# untitled.net
KiCad netlist of a schematic drawn in EAGLE
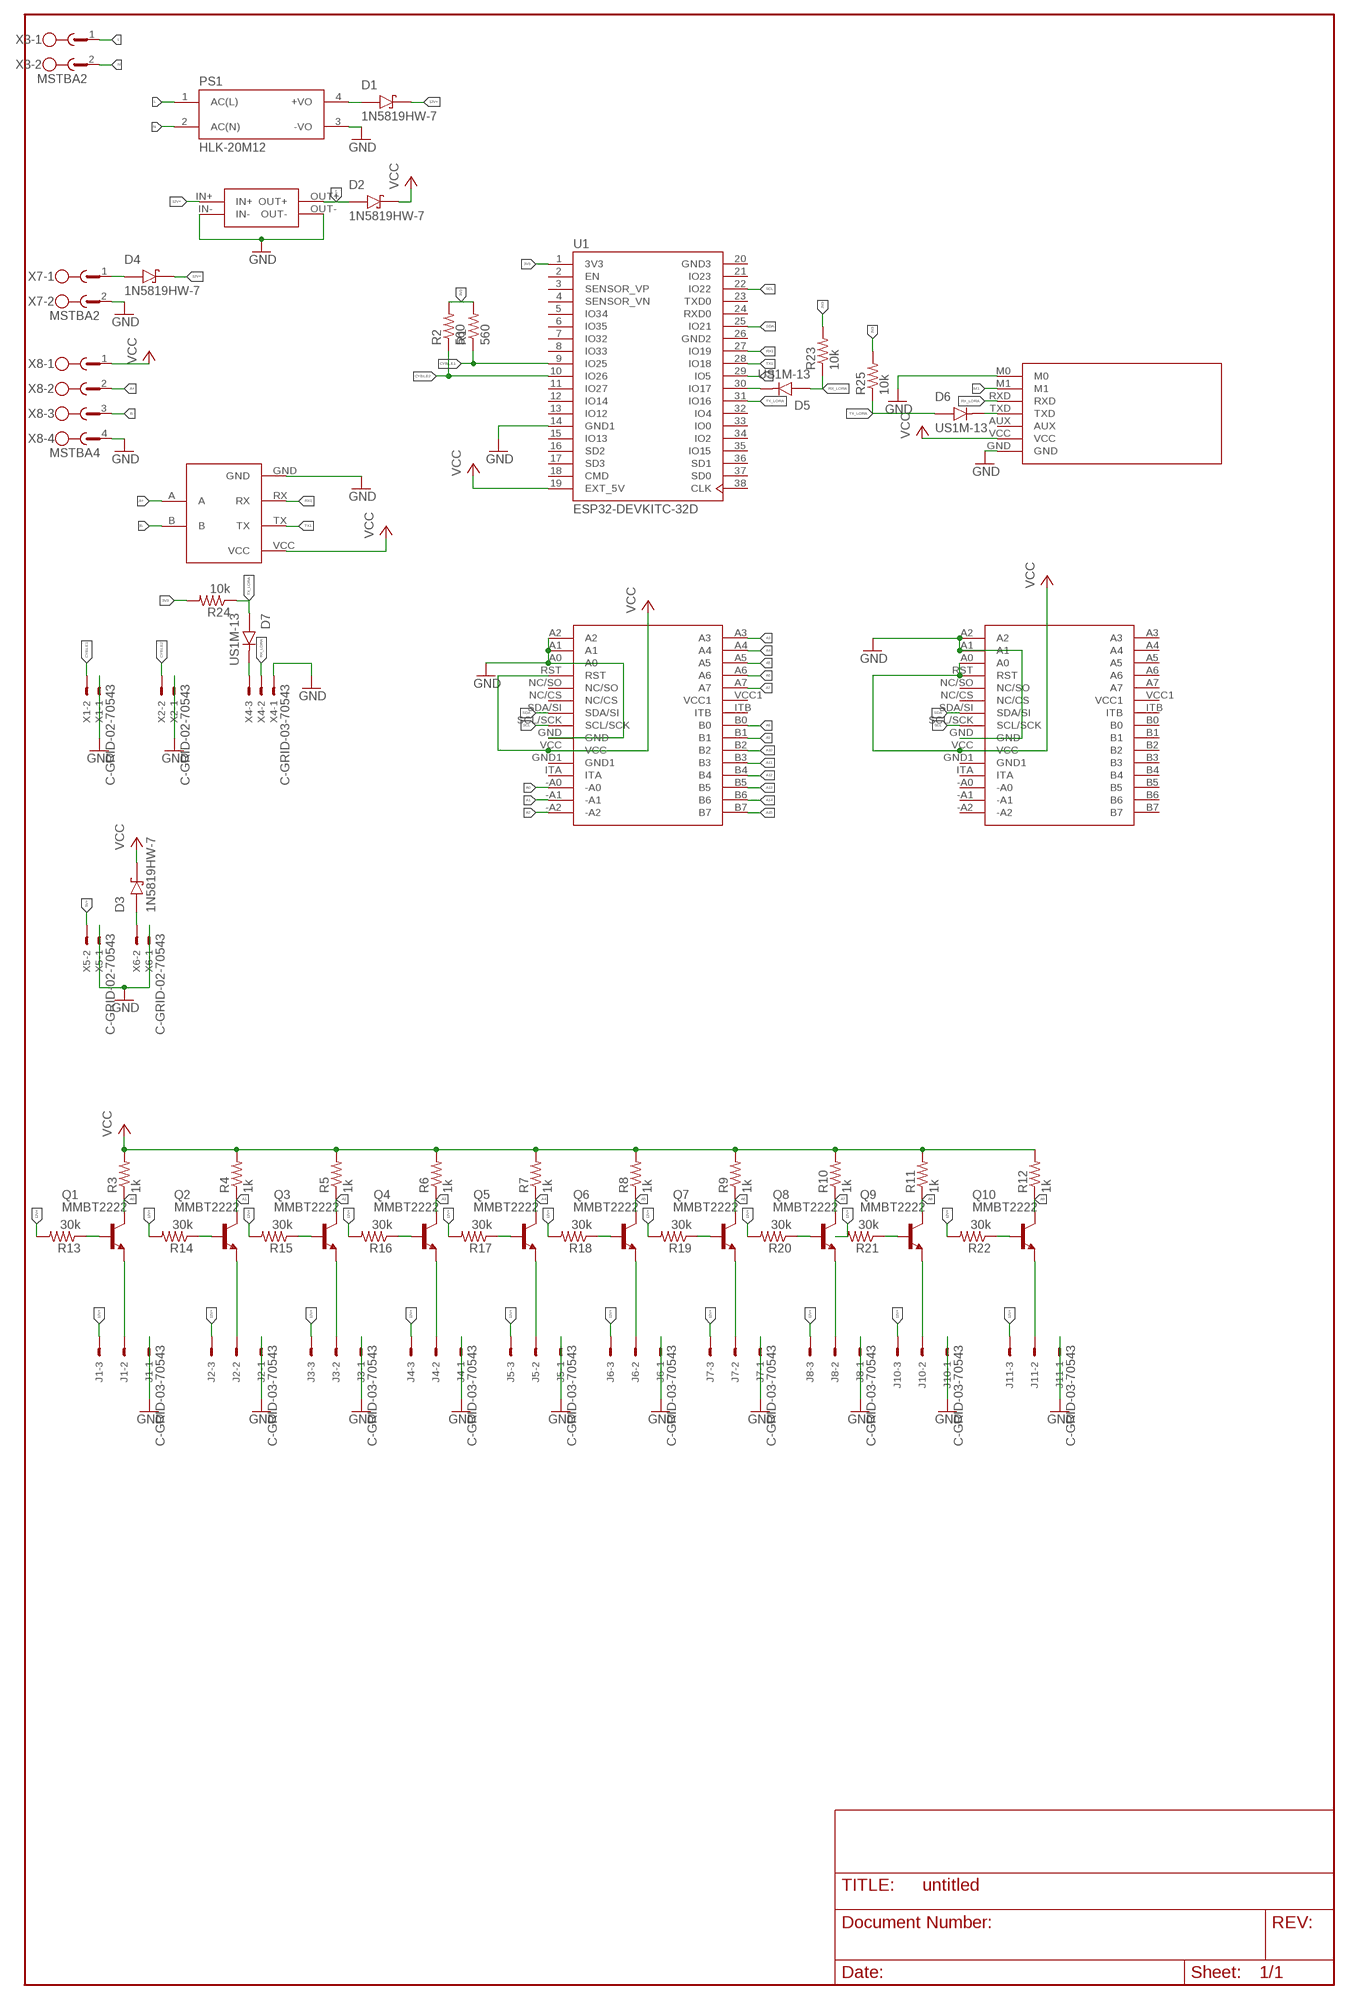
[diagram p0: schematic, sheet 1]

(export (version "E")
  (design (tool "Eeschema 10.0.6"))
  (components
    (comp (ref "D1")
      (value "1N5819HW-7")
      (footprint "eagle-import:SOD3715X145N")
      (fields (field (name "MF") "Diodes Inc."))
      (libsource (lib "eagle-import") (part "1N5819HW-7"))
    )
    (comp (ref "D2")
      (value "1N5819HW-7")
      (footprint "eagle-import:SOD3715X145N")
      (fields (field (name "MF") "Diodes Inc."))
      (libsource (lib "eagle-import") (part "1N5819HW-7"))
    )
    (comp (ref "D3")
      (value "1N5819HW-7")
      (footprint "eagle-import:SOD3715X145N")
      (fields (field (name "MF") "Diodes Inc."))
      (libsource (lib "eagle-import") (part "1N5819HW-7"))
    )
    (comp (ref "D4")
      (value "1N5819HW-7")
      (footprint "eagle-import:SOD3715X145N")
      (fields (field (name "MF") "Diodes Inc."))
      (libsource (lib "eagle-import") (part "1N5819HW-7"))
    )
    (comp (ref "D5")
      (value "US1M-13")
      (footprint "eagle-import:DIOM5226X240N")
      (fields (field (name "MF") "Diodes Incorporated"))
      (libsource (lib "eagle-import") (part "US1M-13"))
    )
    (comp (ref "D6")
      (value "US1M-13")
      (footprint "eagle-import:DIOM5226X240N")
      (fields (field (name "MF") "Diodes Incorporated"))
      (libsource (lib "eagle-import") (part "US1M-13"))
    )
    (comp (ref "D7")
      (value "US1M-13")
      (footprint "eagle-import:DIOM5226X240N")
      (fields (field (name "MF") "Diodes Incorporated"))
      (libsource (lib "eagle-import") (part "US1M-13"))
    )
    (comp (ref "EBYTEE220-900T22D1")
      (value "EBYTEE220-900T22D")
      (footprint "eagle-import:EBYTEE220-900T22D")
      (libsource (lib "eagle-import") (part "EBYTEE220-900T22D"))
    )
    (comp (ref "J1")
      (value "C-GRID-03-70543")
      (footprint "eagle-import:70543-03")
      (fields (field (name "MF") "MOLEX"))
      (libsource (lib "eagle-import") (part "C-GRID-03-70543"))
    )
    (comp (ref "J2")
      (value "C-GRID-03-70543")
      (footprint "eagle-import:70543-03")
      (fields (field (name "MF") "MOLEX"))
      (libsource (lib "eagle-import") (part "C-GRID-03-70543"))
    )
    (comp (ref "J3")
      (value "C-GRID-03-70543")
      (footprint "eagle-import:70543-03")
      (fields (field (name "MF") "MOLEX"))
      (libsource (lib "eagle-import") (part "C-GRID-03-70543"))
    )
    (comp (ref "J4")
      (value "C-GRID-03-70543")
      (footprint "eagle-import:70543-03")
      (fields (field (name "MF") "MOLEX"))
      (libsource (lib "eagle-import") (part "C-GRID-03-70543"))
    )
    (comp (ref "J5")
      (value "C-GRID-03-70543")
      (footprint "eagle-import:70543-03")
      (fields (field (name "MF") "MOLEX"))
      (libsource (lib "eagle-import") (part "C-GRID-03-70543"))
    )
    (comp (ref "J6")
      (value "C-GRID-03-70543")
      (footprint "eagle-import:70543-03")
      (fields (field (name "MF") "MOLEX"))
      (libsource (lib "eagle-import") (part "C-GRID-03-70543"))
    )
    (comp (ref "J7")
      (value "C-GRID-03-70543")
      (footprint "eagle-import:70543-03")
      (fields (field (name "MF") "MOLEX"))
      (libsource (lib "eagle-import") (part "C-GRID-03-70543"))
    )
    (comp (ref "J8")
      (value "C-GRID-03-70543")
      (footprint "eagle-import:70543-03")
      (fields (field (name "MF") "MOLEX"))
      (libsource (lib "eagle-import") (part "C-GRID-03-70543"))
    )
    (comp (ref "J10")
      (value "C-GRID-03-70543")
      (footprint "eagle-import:70543-03")
      (fields (field (name "MF") "MOLEX"))
      (libsource (lib "eagle-import") (part "C-GRID-03-70543"))
    )
    (comp (ref "J11")
      (value "C-GRID-03-70543")
      (footprint "eagle-import:70543-03")
      (fields (field (name "MF") "MOLEX"))
      (libsource (lib "eagle-import") (part "C-GRID-03-70543"))
    )
    (comp (ref "MCP1")
      (value "MCP23017")
      (footprint "eagle-import:MCP23017")
      (libsource (lib "eagle-import") (part "MCP23017"))
    )
    (comp (ref "MCP2")
      (value "MCP23017")
      (footprint "eagle-import:MCP23017")
      (libsource (lib "eagle-import") (part "MCP23017"))
    )
    (comp (ref "MINI1")
      (value "MINI560")
      (footprint "eagle-import:MINI560")
      (libsource (lib "eagle-import") (part "MINI560"))
    )
    (comp (ref "PS1")
      (value "HLK-20M12")
      (footprint "eagle-import:CONV_HLK-20M12")
      (fields (field (name "MF") "Hi-link"))
      (libsource (lib "eagle-import") (part "HLK-20M12"))
    )
    (comp (ref "Q1")
      (value "MMBT2222")
      (footprint "eagle-import:SOT23-BEC")
      (fields (field (name "MF") "ON Semiconductor"))
      (libsource (lib "eagle-import") (part "MMBT2222"))
    )
    (comp (ref "Q2")
      (value "MMBT2222")
      (footprint "eagle-import:SOT23-BEC")
      (fields (field (name "MF") "ON Semiconductor"))
      (libsource (lib "eagle-import") (part "MMBT2222"))
    )
    (comp (ref "Q3")
      (value "MMBT2222")
      (footprint "eagle-import:SOT23-BEC")
      (fields (field (name "MF") "ON Semiconductor"))
      (libsource (lib "eagle-import") (part "MMBT2222"))
    )
    (comp (ref "Q4")
      (value "MMBT2222")
      (footprint "eagle-import:SOT23-BEC")
      (fields (field (name "MF") "ON Semiconductor"))
      (libsource (lib "eagle-import") (part "MMBT2222"))
    )
    (comp (ref "Q5")
      (value "MMBT2222")
      (footprint "eagle-import:SOT23-BEC")
      (fields (field (name "MF") "ON Semiconductor"))
      (libsource (lib "eagle-import") (part "MMBT2222"))
    )
    (comp (ref "Q6")
      (value "MMBT2222")
      (footprint "eagle-import:SOT23-BEC")
      (fields (field (name "MF") "ON Semiconductor"))
      (libsource (lib "eagle-import") (part "MMBT2222"))
    )
    (comp (ref "Q7")
      (value "MMBT2222")
      (footprint "eagle-import:SOT23-BEC")
      (fields (field (name "MF") "ON Semiconductor"))
      (libsource (lib "eagle-import") (part "MMBT2222"))
    )
    (comp (ref "Q8")
      (value "MMBT2222")
      (footprint "eagle-import:SOT23-BEC")
      (fields (field (name "MF") "ON Semiconductor"))
      (libsource (lib "eagle-import") (part "MMBT2222"))
    )
    (comp (ref "Q9")
      (value "MMBT2222")
      (footprint "eagle-import:SOT23-BEC")
      (fields (field (name "MF") "ON Semiconductor"))
      (libsource (lib "eagle-import") (part "MMBT2222"))
    )
    (comp (ref "Q10")
      (value "MMBT2222")
      (footprint "eagle-import:SOT23-BEC")
      (fields (field (name "MF") "ON Semiconductor"))
      (libsource (lib "eagle-import") (part "MMBT2222"))
    )
    (comp (ref "R1")
      (value "560")
      (footprint "eagle-import:M0805")
      (libsource (lib "eagle-import") (part "R-US_M0805"))
    )
    (comp (ref "R2")
      (value "560")
      (footprint "eagle-import:M0805")
      (libsource (lib "eagle-import") (part "R-US_M0805"))
    )
    (comp (ref "R3")
      (value "1k")
      (footprint "eagle-import:M0805")
      (libsource (lib "eagle-import") (part "R-US_M0805"))
    )
    (comp (ref "R4")
      (value "1k")
      (footprint "eagle-import:M0805")
      (libsource (lib "eagle-import") (part "R-US_M0805"))
    )
    (comp (ref "R5")
      (value "1k")
      (footprint "eagle-import:M0805")
      (libsource (lib "eagle-import") (part "R-US_M0805"))
    )
    (comp (ref "R6")
      (value "1k")
      (footprint "eagle-import:M0805")
      (libsource (lib "eagle-import") (part "R-US_M0805"))
    )
    (comp (ref "R7")
      (value "1k")
      (footprint "eagle-import:M0805")
      (libsource (lib "eagle-import") (part "R-US_M0805"))
    )
    (comp (ref "R8")
      (value "1k")
      (footprint "eagle-import:M0805")
      (libsource (lib "eagle-import") (part "R-US_M0805"))
    )
    (comp (ref "R9")
      (value "1k")
      (footprint "eagle-import:M0805")
      (libsource (lib "eagle-import") (part "R-US_M0805"))
    )
    (comp (ref "R10")
      (value "1k")
      (footprint "eagle-import:M0805")
      (libsource (lib "eagle-import") (part "R-US_M0805"))
    )
    (comp (ref "R11")
      (value "1k")
      (footprint "eagle-import:M0805")
      (libsource (lib "eagle-import") (part "R-US_M0805"))
    )
    (comp (ref "R12")
      (value "1k")
      (footprint "eagle-import:M0805")
      (libsource (lib "eagle-import") (part "R-US_M0805"))
    )
    (comp (ref "R13")
      (value "30k")
      (footprint "eagle-import:M0805")
      (libsource (lib "eagle-import") (part "R-US_M0805"))
    )
    (comp (ref "R14")
      (value "30k")
      (footprint "eagle-import:M0805")
      (libsource (lib "eagle-import") (part "R-US_M0805"))
    )
    (comp (ref "R15")
      (value "30k")
      (footprint "eagle-import:M0805")
      (libsource (lib "eagle-import") (part "R-US_M0805"))
    )
    (comp (ref "R16")
      (value "30k")
      (footprint "eagle-import:M0805")
      (libsource (lib "eagle-import") (part "R-US_M0805"))
    )
    (comp (ref "R17")
      (value "30k")
      (footprint "eagle-import:M0805")
      (libsource (lib "eagle-import") (part "R-US_M0805"))
    )
    (comp (ref "R18")
      (value "30k")
      (footprint "eagle-import:M0805")
      (libsource (lib "eagle-import") (part "R-US_M0805"))
    )
    (comp (ref "R19")
      (value "30k")
      (footprint "eagle-import:M0805")
      (libsource (lib "eagle-import") (part "R-US_M0805"))
    )
    (comp (ref "R20")
      (value "30k")
      (footprint "eagle-import:M0805")
      (libsource (lib "eagle-import") (part "R-US_M0805"))
    )
    (comp (ref "R21")
      (value "30k")
      (footprint "eagle-import:M0805")
      (libsource (lib "eagle-import") (part "R-US_M0805"))
    )
    (comp (ref "R22")
      (value "30k")
      (footprint "eagle-import:M0805")
      (libsource (lib "eagle-import") (part "R-US_M0805"))
    )
    (comp (ref "R23")
      (value "10k")
      (footprint "eagle-import:M0805")
      (libsource (lib "eagle-import") (part "R-US_M0805"))
    )
    (comp (ref "R24")
      (value "10k")
      (footprint "eagle-import:M0805")
      (libsource (lib "eagle-import") (part "R-US_M0805"))
    )
    (comp (ref "R25")
      (value "10k")
      (footprint "eagle-import:M0805")
      (libsource (lib "eagle-import") (part "R-US_M0805"))
    )
    (comp (ref "TTL-RS1")
      (value "TTL-RS485")
      (footprint "eagle-import:TTL-RS485")
      (libsource (lib "eagle-import") (part "TTL-RS485"))
    )
    (comp (ref "U1")
      (value "ESP32-DEVKITC-32D")
      (footprint "eagle-import:MODULE_ESP32-DEVKITC-32D")
      (fields (field (name "MF") "Espressif Systems"))
      (libsource (lib "eagle-import") (part "ESP32-DEVKITC-32D"))
    )
    (comp (ref "X1")
      (value "C-GRID-02-70543")
      (footprint "eagle-import:70543-02")
      (fields (field (name "MF") "MOLEX"))
      (libsource (lib "eagle-import") (part "C-GRID-02-70543"))
    )
    (comp (ref "X2")
      (value "C-GRID-02-70543")
      (footprint "eagle-import:70543-02")
      (fields (field (name "MF") "MOLEX"))
      (libsource (lib "eagle-import") (part "C-GRID-02-70543"))
    )
    (comp (ref "X3")
      (value "MSTBA2")
      (footprint "eagle-import:MSTBA2")
      (fields (field (name "MF") "FARNELL") (field (name "MPN") "1757242"))
      (libsource (lib "eagle-import") (part "MSTBA2"))
    )
    (comp (ref "X4")
      (value "C-GRID-03-70543")
      (footprint "eagle-import:70543-03")
      (fields (field (name "MF") "MOLEX"))
      (libsource (lib "eagle-import") (part "C-GRID-03-70543"))
    )
    (comp (ref "X5")
      (value "C-GRID-02-70543")
      (footprint "eagle-import:70543-02")
      (fields (field (name "MF") "MOLEX"))
      (libsource (lib "eagle-import") (part "C-GRID-02-70543"))
    )
    (comp (ref "X6")
      (value "C-GRID-02-70543")
      (footprint "eagle-import:70543-02")
      (fields (field (name "MF") "MOLEX"))
      (libsource (lib "eagle-import") (part "C-GRID-02-70543"))
    )
    (comp (ref "X7")
      (value "MSTBA2")
      (footprint "eagle-import:MSTBA2")
      (fields (field (name "MF") "FARNELL") (field (name "MPN") "1757242"))
      (libsource (lib "eagle-import") (part "MSTBA2"))
    )
    (comp (ref "X8")
      (value "MSTBA4")
      (footprint "eagle-import:MSTBA4")
      (fields (field (name "MF") "FARNELL") (field (name "MPN") "1757268"))
      (libsource (lib "eagle-import") (part "MSTBA4"))
    )
  )
  (nets
    (net (code "1") (name "/GND2") (class "Default")
      (node (ref "U1") (pin "26") (pinfunction "GND2_26") (pintype "power_in"))
    )
    (net (code "2") (name "/GND3") (class "Default")
      (node (ref "U1") (pin "20") (pinfunction "GND3_20") (pintype "power_in"))
    )
    (net (code "3") (name "3V3") (class "Default")
      (node (ref "R1") (pin "2") (pinfunction "2_2") (pintype "passive"))
      (node (ref "R2") (pin "2") (pinfunction "2_2") (pintype "passive"))
      (node (ref "R23") (pin "2") (pinfunction "2_2") (pintype "passive"))
      (node (ref "R24") (pin "2") (pinfunction "2_2") (pintype "passive"))
      (node (ref "R25") (pin "2") (pinfunction "2_2") (pintype "passive"))
      (node (ref "U1") (pin "1") (pinfunction "3V3_1") (pintype "power_in"))
    )
    (net (code "4") (name "5V+") (class "Default")
      (node (ref "D2") (pin "A") (pinfunction "A_A") (pintype "passive"))
      (node (ref "MINI1") (pin "OUT+") (pinfunction "OUT+_OUT+") (pintype "bidirectional"))
      (node (ref "X5") (pin "2") (pinfunction "S_2") (pintype "passive"))
    )
    (net (code "5") (name "12V+") (class "Default")
      (node (ref "D1") (pin "C") (pinfunction "K_C") (pintype "passive"))
      (node (ref "D4") (pin "C") (pinfunction "K_C") (pintype "passive"))
      (node (ref "J1") (pin "3") (pinfunction "S_3") (pintype "passive"))
      (node (ref "J10") (pin "3") (pinfunction "S_3") (pintype "passive"))
      (node (ref "J11") (pin "3") (pinfunction "S_3") (pintype "passive"))
      (node (ref "J2") (pin "3") (pinfunction "S_3") (pintype "passive"))
      (node (ref "J3") (pin "3") (pinfunction "S_3") (pintype "passive"))
      (node (ref "J4") (pin "3") (pinfunction "S_3") (pintype "passive"))
      (node (ref "J5") (pin "3") (pinfunction "S_3") (pintype "passive"))
      (node (ref "J6") (pin "3") (pinfunction "S_3") (pintype "passive"))
      (node (ref "J7") (pin "3") (pinfunction "S_3") (pintype "passive"))
      (node (ref "J8") (pin "3") (pinfunction "S_3") (pintype "passive"))
      (node (ref "MINI1") (pin "IN+") (pinfunction "IN+_IN+") (pintype "bidirectional"))
      (node (ref "R13") (pin "2") (pinfunction "2_2") (pintype "passive"))
      (node (ref "R14") (pin "2") (pinfunction "2_2") (pintype "passive"))
      (node (ref "R15") (pin "2") (pinfunction "2_2") (pintype "passive"))
      (node (ref "R16") (pin "2") (pinfunction "2_2") (pintype "passive"))
      (node (ref "R17") (pin "2") (pinfunction "2_2") (pintype "passive"))
      (node (ref "R18") (pin "2") (pinfunction "2_2") (pintype "passive"))
      (node (ref "R19") (pin "2") (pinfunction "2_2") (pintype "passive"))
      (node (ref "R20") (pin "2") (pinfunction "2_2") (pintype "passive"))
      (node (ref "R21") (pin "2") (pinfunction "2_2") (pintype "passive"))
      (node (ref "R22") (pin "2") (pinfunction "2_2") (pintype "passive"))
    )
    (net (code "6") (name "A+") (class "Default")
      (node (ref "TTL-RS1") (pin "A") (pinfunction "A_A") (pintype "bidirectional"))
      (node (ref "X8") (pin "2") (pinfunction "1_2") (pintype "passive"))
    )
    (net (code "7") (name "A0") (class "Default")
      (node (ref "MCP1") (pin "-A0") (pinfunction "-A0_-A0") (pintype "bidirectional"))
      (node (ref "Q1") (pin "C") (pinfunction "C_C") (pintype "passive"))
      (node (ref "R3") (pin "1") (pinfunction "1_1") (pintype "passive"))
    )
    (net (code "8") (name "A1") (class "Default")
      (node (ref "MCP1") (pin "-A1") (pinfunction "-A1_-A1") (pintype "bidirectional"))
      (node (ref "Q2") (pin "C") (pinfunction "C_C") (pintype "passive"))
      (node (ref "R4") (pin "1") (pinfunction "1_1") (pintype "passive"))
    )
    (net (code "9") (name "A2") (class "Default")
      (node (ref "MCP1") (pin "-A2") (pinfunction "-A2_-A2") (pintype "bidirectional"))
      (node (ref "Q3") (pin "C") (pinfunction "C_C") (pintype "passive"))
      (node (ref "R5") (pin "1") (pinfunction "1_1") (pintype "passive"))
    )
    (net (code "10") (name "A3") (class "Default")
      (node (ref "MCP1") (pin "A3") (pinfunction "A3_A3") (pintype "bidirectional"))
      (node (ref "Q4") (pin "C") (pinfunction "C_C") (pintype "passive"))
      (node (ref "R6") (pin "1") (pinfunction "1_1") (pintype "passive"))
    )
    (net (code "11") (name "A4") (class "Default")
      (node (ref "MCP1") (pin "A4") (pinfunction "A4_A4") (pintype "bidirectional"))
      (node (ref "Q5") (pin "C") (pinfunction "C_C") (pintype "passive"))
      (node (ref "R7") (pin "1") (pinfunction "1_1") (pintype "passive"))
    )
    (net (code "12") (name "A5") (class "Default")
      (node (ref "MCP1") (pin "A5") (pinfunction "A5_A5") (pintype "bidirectional"))
      (node (ref "Q6") (pin "C") (pinfunction "C_C") (pintype "passive"))
      (node (ref "R8") (pin "1") (pinfunction "1_1") (pintype "passive"))
    )
    (net (code "13") (name "A6") (class "Default")
      (node (ref "MCP1") (pin "A6") (pinfunction "A6_A6") (pintype "bidirectional"))
      (node (ref "Q7") (pin "C") (pinfunction "C_C") (pintype "passive"))
      (node (ref "R9") (pin "1") (pinfunction "1_1") (pintype "passive"))
    )
    (net (code "14") (name "A7") (class "Default")
      (node (ref "MCP1") (pin "A7") (pinfunction "A7_A7") (pintype "bidirectional"))
      (node (ref "Q8") (pin "C") (pinfunction "C_C") (pintype "passive"))
      (node (ref "R10") (pin "1") (pinfunction "1_1") (pintype "passive"))
    )
    (net (code "15") (name "A8") (class "Default")
      (node (ref "MCP1") (pin "B0") (pinfunction "B0_B0") (pintype "bidirectional"))
      (node (ref "Q9") (pin "C") (pinfunction "C_C") (pintype "passive"))
      (node (ref "R11") (pin "1") (pinfunction "1_1") (pintype "passive"))
    )
    (net (code "16") (name "A9") (class "Default")
      (node (ref "MCP1") (pin "B1") (pinfunction "B1_B1") (pintype "bidirectional"))
      (node (ref "Q10") (pin "C") (pinfunction "C_C") (pintype "passive"))
      (node (ref "R12") (pin "1") (pinfunction "1_1") (pintype "passive"))
    )
    (net (code "17") (name "A10") (class "Default")
      (node (ref "MCP1") (pin "B2") (pinfunction "B2_B2") (pintype "bidirectional"))
    )
    (net (code "18") (name "A11") (class "Default")
      (node (ref "MCP1") (pin "B3") (pinfunction "B3_B3") (pintype "bidirectional"))
    )
    (net (code "19") (name "A12") (class "Default")
      (node (ref "MCP1") (pin "B4") (pinfunction "B4_B4") (pintype "bidirectional"))
    )
    (net (code "20") (name "A13") (class "Default")
      (node (ref "MCP1") (pin "B5") (pinfunction "B5_B5") (pintype "bidirectional"))
    )
    (net (code "21") (name "A14") (class "Default")
      (node (ref "MCP1") (pin "B6") (pinfunction "B6_B6") (pintype "bidirectional"))
    )
    (net (code "22") (name "A15") (class "Default")
      (node (ref "MCP1") (pin "B7") (pinfunction "B7_B7") (pintype "bidirectional"))
    )
    (net (code "23") (name "B-") (class "Default")
      (node (ref "TTL-RS1") (pin "B") (pinfunction "B_B") (pintype "bidirectional"))
      (node (ref "X8") (pin "3") (pinfunction "1_3") (pintype "passive"))
    )
    (net (code "24") (name "CYBLE1") (class "Default")
      (node (ref "R1") (pin "1") (pinfunction "1_1") (pintype "passive"))
      (node (ref "U1") (pin "9") (pinfunction "IO25_9") (pintype "bidirectional"))
      (node (ref "X1") (pin "2") (pinfunction "S_2") (pintype "passive"))
    )
    (net (code "25") (name "CYBLE2") (class "Default")
      (node (ref "R2") (pin "1") (pinfunction "1_1") (pintype "passive"))
      (node (ref "U1") (pin "10") (pinfunction "IO26_10") (pintype "bidirectional"))
      (node (ref "X2") (pin "2") (pinfunction "S_2") (pintype "passive"))
    )
    (net (code "26") (name "GND") (class "Default")
      (node (ref "EBYTEE220-900T22D1") (pin "GND") (pinfunction "GND_GND") (pintype "bidirectional"))
      (node (ref "EBYTEE220-900T22D1") (pin "M0") (pinfunction "M0_M0") (pintype "bidirectional"))
      (node (ref "J1") (pin "1") (pinfunction "S_1") (pintype "passive"))
      (node (ref "J10") (pin "1") (pinfunction "S_1") (pintype "passive"))
      (node (ref "J11") (pin "1") (pinfunction "S_1") (pintype "passive"))
      (node (ref "J2") (pin "1") (pinfunction "S_1") (pintype "passive"))
      (node (ref "J3") (pin "1") (pinfunction "S_1") (pintype "passive"))
      (node (ref "J4") (pin "1") (pinfunction "S_1") (pintype "passive"))
      (node (ref "J5") (pin "1") (pinfunction "S_1") (pintype "passive"))
      (node (ref "J6") (pin "1") (pinfunction "S_1") (pintype "passive"))
      (node (ref "J7") (pin "1") (pinfunction "S_1") (pintype "passive"))
      (node (ref "J8") (pin "1") (pinfunction "S_1") (pintype "passive"))
      (node (ref "MCP1") (pin "A0") (pinfunction "A0_A0") (pintype "bidirectional"))
      (node (ref "MCP1") (pin "A1") (pinfunction "A1_A1") (pintype "bidirectional"))
      (node (ref "MCP1") (pin "A2") (pinfunction "A2_A2") (pintype "bidirectional"))
      (node (ref "MCP1") (pin "GND") (pinfunction "GND_GND") (pintype "bidirectional"))
      (node (ref "MCP2") (pin "A1") (pinfunction "A1_A1") (pintype "bidirectional"))
      (node (ref "MCP2") (pin "A2") (pinfunction "A2_A2") (pintype "bidirectional"))
      (node (ref "MCP2") (pin "GND") (pinfunction "GND_GND") (pintype "bidirectional"))
      (node (ref "MINI1") (pin "IN-") (pinfunction "IN-_IN-") (pintype "bidirectional"))
      (node (ref "MINI1") (pin "OUT-") (pinfunction "OUT-_OUT-") (pintype "bidirectional"))
      (node (ref "PS1") (pin "3") (pinfunction "-VO_3") (pintype "output"))
      (node (ref "TTL-RS1") (pin "GND") (pinfunction "GND_GND") (pintype "bidirectional"))
      (node (ref "U1") (pin "14") (pinfunction "GND1_14") (pintype "power_in"))
      (node (ref "X1") (pin "1") (pinfunction "S_1") (pintype "passive"))
      (node (ref "X2") (pin "1") (pinfunction "S_1") (pintype "passive"))
      (node (ref "X4") (pin "1") (pinfunction "S_1") (pintype "passive"))
      (node (ref "X5") (pin "1") (pinfunction "S_1") (pintype "passive"))
      (node (ref "X6") (pin "1") (pinfunction "S_1") (pintype "passive"))
      (node (ref "X7") (pin "2") (pinfunction "1_2") (pintype "passive"))
      (node (ref "X8") (pin "4") (pinfunction "1_4") (pintype "passive"))
    )
    (net (code "27") (name "L") (class "Default")
      (node (ref "PS1") (pin "1") (pinfunction "AC(L)_1") (pintype "input"))
      (node (ref "X3") (pin "1") (pinfunction "1_1") (pintype "passive"))
    )
    (net (code "28") (name "M1") (class "Default")
      (node (ref "EBYTEE220-900T22D1") (pin "M1") (pinfunction "M1_M1") (pintype "bidirectional"))
      (node (ref "U1") (pin "29") (pinfunction "IO5_29") (pintype "bidirectional"))
    )
    (net (code "29") (name "N") (class "Default")
      (node (ref "PS1") (pin "2") (pinfunction "AC(N)_2") (pintype "input"))
      (node (ref "X3") (pin "2") (pinfunction "1_2") (pintype "passive"))
    )
    (net (code "30") (name "Net-(D4-PadA)") (class "Default")
      (node (ref "D4") (pin "A") (pinfunction "A_A") (pintype "passive"))
      (node (ref "X7") (pin "1") (pinfunction "1_1") (pintype "passive"))
    )
    (net (code "31") (name "Net-(D5-K)") (class "Default")
      (node (ref "D5") (pin "C") (pinfunction "K_C") (pintype "passive"))
      (node (ref "U1") (pin "30") (pinfunction "IO17_30") (pintype "bidirectional"))
    )
    (net (code "32") (name "Net-(D6-K)") (class "Default")
      (node (ref "D6") (pin "C") (pinfunction "K_C") (pintype "passive"))
      (node (ref "EBYTEE220-900T22D1") (pin "TXD") (pinfunction "TXD_TXD") (pintype "bidirectional"))
    )
    (net (code "33") (name "Net-(D7-K)") (class "Default")
      (node (ref "D7") (pin "C") (pinfunction "K_C") (pintype "passive"))
      (node (ref "X4") (pin "3") (pinfunction "S_3") (pintype "passive"))
    )
    (net (code "34") (name "Net-(J1B-S)") (class "Default")
      (node (ref "J1") (pin "2") (pinfunction "S_2") (pintype "passive"))
      (node (ref "Q1") (pin "E") (pinfunction "E_E") (pintype "passive"))
    )
    (net (code "35") (name "Net-(J2B-S)") (class "Default")
      (node (ref "J2") (pin "2") (pinfunction "S_2") (pintype "passive"))
      (node (ref "Q2") (pin "E") (pinfunction "E_E") (pintype "passive"))
    )
    (net (code "36") (name "Net-(J3B-S)") (class "Default")
      (node (ref "J3") (pin "2") (pinfunction "S_2") (pintype "passive"))
      (node (ref "Q3") (pin "E") (pinfunction "E_E") (pintype "passive"))
    )
    (net (code "37") (name "Net-(J4B-S)") (class "Default")
      (node (ref "J4") (pin "2") (pinfunction "S_2") (pintype "passive"))
      (node (ref "Q4") (pin "E") (pinfunction "E_E") (pintype "passive"))
    )
    (net (code "38") (name "Net-(J5B-S)") (class "Default")
      (node (ref "J5") (pin "2") (pinfunction "S_2") (pintype "passive"))
      (node (ref "Q5") (pin "E") (pinfunction "E_E") (pintype "passive"))
    )
    (net (code "39") (name "Net-(J6B-S)") (class "Default")
      (node (ref "J6") (pin "2") (pinfunction "S_2") (pintype "passive"))
      (node (ref "Q6") (pin "E") (pinfunction "E_E") (pintype "passive"))
    )
    (net (code "40") (name "Net-(J7B-S)") (class "Default")
      (node (ref "J7") (pin "2") (pinfunction "S_2") (pintype "passive"))
      (node (ref "Q7") (pin "E") (pinfunction "E_E") (pintype "passive"))
    )
    (net (code "41") (name "Net-(J8B-S)") (class "Default")
      (node (ref "J8") (pin "2") (pinfunction "S_2") (pintype "passive"))
      (node (ref "Q8") (pin "E") (pinfunction "E_E") (pintype "passive"))
    )
    (net (code "42") (name "Net-(J10B-S)") (class "Default")
      (node (ref "J10") (pin "2") (pinfunction "S_2") (pintype "passive"))
      (node (ref "Q9") (pin "E") (pinfunction "E_E") (pintype "passive"))
    )
    (net (code "43") (name "Net-(J11B-S)") (class "Default")
      (node (ref "J11") (pin "2") (pinfunction "S_2") (pintype "passive"))
      (node (ref "Q10") (pin "E") (pinfunction "E_E") (pintype "passive"))
    )
    (net (code "44") (name "Net-(PS1-+VO)") (class "Default")
      (node (ref "D1") (pin "A") (pinfunction "A_A") (pintype "passive"))
      (node (ref "PS1") (pin "4") (pinfunction "+VO_4") (pintype "output"))
    )
    (net (code "45") (name "Net-(Q1-PadB)") (class "Default")
      (node (ref "Q1") (pin "B") (pinfunction "B_B") (pintype "passive"))
      (node (ref "R13") (pin "1") (pinfunction "1_1") (pintype "passive"))
    )
    (net (code "46") (name "Net-(Q2-PadB)") (class "Default")
      (node (ref "Q2") (pin "B") (pinfunction "B_B") (pintype "passive"))
      (node (ref "R14") (pin "1") (pinfunction "1_1") (pintype "passive"))
    )
    (net (code "47") (name "Net-(Q3-PadB)") (class "Default")
      (node (ref "Q3") (pin "B") (pinfunction "B_B") (pintype "passive"))
      (node (ref "R15") (pin "1") (pinfunction "1_1") (pintype "passive"))
    )
    (net (code "48") (name "Net-(Q4-PadB)") (class "Default")
      (node (ref "Q4") (pin "B") (pinfunction "B_B") (pintype "passive"))
      (node (ref "R16") (pin "1") (pinfunction "1_1") (pintype "passive"))
    )
    (net (code "49") (name "Net-(Q5-PadB)") (class "Default")
      (node (ref "Q5") (pin "B") (pinfunction "B_B") (pintype "passive"))
      (node (ref "R17") (pin "1") (pinfunction "1_1") (pintype "passive"))
    )
    (net (code "50") (name "Net-(Q6-PadB)") (class "Default")
      (node (ref "Q6") (pin "B") (pinfunction "B_B") (pintype "passive"))
      (node (ref "R18") (pin "1") (pinfunction "1_1") (pintype "passive"))
    )
    (net (code "51") (name "Net-(Q7-PadB)") (class "Default")
      (node (ref "Q7") (pin "B") (pinfunction "B_B") (pintype "passive"))
      (node (ref "R19") (pin "1") (pinfunction "1_1") (pintype "passive"))
    )
    (net (code "52") (name "Net-(Q8-PadB)") (class "Default")
      (node (ref "Q8") (pin "B") (pinfunction "B_B") (pintype "passive"))
      (node (ref "R20") (pin "1") (pinfunction "1_1") (pintype "passive"))
    )
    (net (code "53") (name "Net-(Q9-PadB)") (class "Default")
      (node (ref "Q9") (pin "B") (pinfunction "B_B") (pintype "passive"))
      (node (ref "R21") (pin "1") (pinfunction "1_1") (pintype "passive"))
    )
    (net (code "54") (name "Net-(Q10-PadB)") (class "Default")
      (node (ref "Q10") (pin "B") (pinfunction "B_B") (pintype "passive"))
      (node (ref "R22") (pin "1") (pinfunction "1_1") (pintype "passive"))
    )
    (net (code "55") (name "Net-(X6B-S)") (class "Default")
      (node (ref "D3") (pin "A") (pinfunction "A_A") (pintype "passive"))
      (node (ref "X6") (pin "2") (pinfunction "S_2") (pintype "passive"))
    )
    (net (code "56") (name "RX1") (class "Default")
      (node (ref "TTL-RS1") (pin "RX") (pinfunction "RX_RX") (pintype "bidirectional"))
      (node (ref "U1") (pin "27") (pinfunction "IO19_27") (pintype "bidirectional"))
    )
    (net (code "57") (name "RX_LORA") (class "Default")
      (node (ref "D5") (pin "A") (pinfunction "A_A") (pintype "passive"))
      (node (ref "EBYTEE220-900T22D1") (pin "RXD") (pinfunction "RXD_RXD") (pintype "bidirectional"))
      (node (ref "R23") (pin "1") (pinfunction "1_1") (pintype "passive"))
      (node (ref "X4") (pin "2") (pinfunction "S_2") (pintype "passive"))
    )
    (net (code "58") (name "SCL") (class "Default")
      (node (ref "MCP1") (pin "SCL/SCK") (pinfunction "SCL/SCK_SCL/SCK") (pintype "bidirectional"))
      (node (ref "MCP2") (pin "SCL/SCK") (pinfunction "SCL/SCK_SCL/SCK") (pintype "bidirectional"))
      (node (ref "U1") (pin "22") (pinfunction "IO22_22") (pintype "bidirectional"))
    )
    (net (code "59") (name "SDA") (class "Default")
      (node (ref "MCP1") (pin "SDA/SI") (pinfunction "SDA/SI_SDA/SI") (pintype "bidirectional"))
      (node (ref "MCP2") (pin "SDA/SI") (pinfunction "SDA/SI_SDA/SI") (pintype "bidirectional"))
      (node (ref "U1") (pin "25") (pinfunction "IO21_25") (pintype "bidirectional"))
    )
    (net (code "60") (name "TX1") (class "Default")
      (node (ref "TTL-RS1") (pin "TX") (pinfunction "TX_TX") (pintype "bidirectional"))
      (node (ref "U1") (pin "28") (pinfunction "IO18_28") (pintype "bidirectional"))
    )
    (net (code "61") (name "TX_LORA") (class "Default")
      (node (ref "D6") (pin "A") (pinfunction "A_A") (pintype "passive"))
      (node (ref "D7") (pin "A") (pinfunction "A_A") (pintype "passive"))
      (node (ref "R24") (pin "1") (pinfunction "1_1") (pintype "passive"))
      (node (ref "R25") (pin "1") (pinfunction "1_1") (pintype "passive"))
      (node (ref "U1") (pin "31") (pinfunction "IO16_31") (pintype "bidirectional"))
    )
    (net (code "62") (name "VCC") (class "Default")
      (node (ref "D2") (pin "C") (pinfunction "K_C") (pintype "passive"))
      (node (ref "D3") (pin "C") (pinfunction "K_C") (pintype "passive"))
      (node (ref "EBYTEE220-900T22D1") (pin "VCC") (pinfunction "VCC_VCC") (pintype "bidirectional"))
      (node (ref "MCP1") (pin "RST") (pinfunction "RST_RST") (pintype "bidirectional"))
      (node (ref "MCP1") (pin "VCC") (pinfunction "VCC_VCC") (pintype "bidirectional"))
      (node (ref "MCP2") (pin "A0") (pinfunction "A0_A0") (pintype "bidirectional"))
      (node (ref "MCP2") (pin "RST") (pinfunction "RST_RST") (pintype "bidirectional"))
      (node (ref "MCP2") (pin "VCC") (pinfunction "VCC_VCC") (pintype "bidirectional"))
      (node (ref "R10") (pin "2") (pinfunction "2_2") (pintype "passive"))
      (node (ref "R11") (pin "2") (pinfunction "2_2") (pintype "passive"))
      (node (ref "R12") (pin "2") (pinfunction "2_2") (pintype "passive"))
      (node (ref "R3") (pin "2") (pinfunction "2_2") (pintype "passive"))
      (node (ref "R4") (pin "2") (pinfunction "2_2") (pintype "passive"))
      (node (ref "R5") (pin "2") (pinfunction "2_2") (pintype "passive"))
      (node (ref "R6") (pin "2") (pinfunction "2_2") (pintype "passive"))
      (node (ref "R7") (pin "2") (pinfunction "2_2") (pintype "passive"))
      (node (ref "R8") (pin "2") (pinfunction "2_2") (pintype "passive"))
      (node (ref "R9") (pin "2") (pinfunction "2_2") (pintype "passive"))
      (node (ref "TTL-RS1") (pin "VCC") (pinfunction "VCC_VCC") (pintype "bidirectional"))
      (node (ref "U1") (pin "19") (pinfunction "EXT_5V_19") (pintype "power_in"))
      (node (ref "X8") (pin "1") (pinfunction "1_1") (pintype "passive"))
    )
    (net (code "63") (name "unconnected-(EBYTEE220-900T22D1-PadAUX)") (class "Default")
      (node (ref "EBYTEE220-900T22D1") (pin "AUX") (pinfunction "AUX_AUX") (pintype "bidirectional"))
    )
    (net (code "64") (name "unconnected-(MCP1-PadGND1)") (class "Default")
      (node (ref "MCP1") (pin "GND1") (pinfunction "GND1_GND1") (pintype "bidirectional"))
    )
    (net (code "65") (name "unconnected-(MCP1-PadITA)") (class "Default")
      (node (ref "MCP1") (pin "ITA") (pinfunction "ITA_ITA") (pintype "bidirectional"))
    )
    (net (code "66") (name "unconnected-(MCP1-PadITB)") (class "Default")
      (node (ref "MCP1") (pin "ITB") (pinfunction "ITB_ITB") (pintype "bidirectional"))
    )
    (net (code "67") (name "unconnected-(MCP1-PadNC{slash}CS)") (class "Default")
      (node (ref "MCP1") (pin "NC/CS") (pinfunction "NC/CS_NC/CS") (pintype "bidirectional"))
    )
    (net (code "68") (name "unconnected-(MCP1-PadNC{slash}SO)") (class "Default")
      (node (ref "MCP1") (pin "NC/SO") (pinfunction "NC/SO_NC/SO") (pintype "bidirectional"))
    )
    (net (code "69") (name "unconnected-(MCP1-PadVCC1)") (class "Default")
      (node (ref "MCP1") (pin "VCC1") (pinfunction "VCC1_VCC1") (pintype "bidirectional"))
    )
    (net (code "70") (name "unconnected-(MCP2-Pad-A0)") (class "Default")
      (node (ref "MCP2") (pin "-A0") (pinfunction "-A0_-A0") (pintype "bidirectional"))
    )
    (net (code "71") (name "unconnected-(MCP2-Pad-A1)") (class "Default")
      (node (ref "MCP2") (pin "-A1") (pinfunction "-A1_-A1") (pintype "bidirectional"))
    )
    (net (code "72") (name "unconnected-(MCP2-Pad-A2)") (class "Default")
      (node (ref "MCP2") (pin "-A2") (pinfunction "-A2_-A2") (pintype "bidirectional"))
    )
    (net (code "73") (name "unconnected-(MCP2-PadA3)") (class "Default")
      (node (ref "MCP2") (pin "A3") (pinfunction "A3_A3") (pintype "bidirectional"))
    )
    (net (code "74") (name "unconnected-(MCP2-PadA4)") (class "Default")
      (node (ref "MCP2") (pin "A4") (pinfunction "A4_A4") (pintype "bidirectional"))
    )
    (net (code "75") (name "unconnected-(MCP2-PadA5)") (class "Default")
      (node (ref "MCP2") (pin "A5") (pinfunction "A5_A5") (pintype "bidirectional"))
    )
    (net (code "76") (name "unconnected-(MCP2-PadA6)") (class "Default")
      (node (ref "MCP2") (pin "A6") (pinfunction "A6_A6") (pintype "bidirectional"))
    )
    (net (code "77") (name "unconnected-(MCP2-PadA7)") (class "Default")
      (node (ref "MCP2") (pin "A7") (pinfunction "A7_A7") (pintype "bidirectional"))
    )
    (net (code "78") (name "unconnected-(MCP2-PadB0)") (class "Default")
      (node (ref "MCP2") (pin "B0") (pinfunction "B0_B0") (pintype "bidirectional"))
    )
    (net (code "79") (name "unconnected-(MCP2-PadB1)") (class "Default")
      (node (ref "MCP2") (pin "B1") (pinfunction "B1_B1") (pintype "bidirectional"))
    )
    (net (code "80") (name "unconnected-(MCP2-PadB2)") (class "Default")
      (node (ref "MCP2") (pin "B2") (pinfunction "B2_B2") (pintype "bidirectional"))
    )
    (net (code "81") (name "unconnected-(MCP2-PadB3)") (class "Default")
      (node (ref "MCP2") (pin "B3") (pinfunction "B3_B3") (pintype "bidirectional"))
    )
    (net (code "82") (name "unconnected-(MCP2-PadB4)") (class "Default")
      (node (ref "MCP2") (pin "B4") (pinfunction "B4_B4") (pintype "bidirectional"))
    )
    (net (code "83") (name "unconnected-(MCP2-PadB5)") (class "Default")
      (node (ref "MCP2") (pin "B5") (pinfunction "B5_B5") (pintype "bidirectional"))
    )
    (net (code "84") (name "unconnected-(MCP2-PadB6)") (class "Default")
      (node (ref "MCP2") (pin "B6") (pinfunction "B6_B6") (pintype "bidirectional"))
    )
    (net (code "85") (name "unconnected-(MCP2-PadB7)") (class "Default")
      (node (ref "MCP2") (pin "B7") (pinfunction "B7_B7") (pintype "bidirectional"))
    )
    (net (code "86") (name "unconnected-(MCP2-PadGND1)") (class "Default")
      (node (ref "MCP2") (pin "GND1") (pinfunction "GND1_GND1") (pintype "bidirectional"))
    )
    (net (code "87") (name "unconnected-(MCP2-PadITA)") (class "Default")
      (node (ref "MCP2") (pin "ITA") (pinfunction "ITA_ITA") (pintype "bidirectional"))
    )
    (net (code "88") (name "unconnected-(MCP2-PadITB)") (class "Default")
      (node (ref "MCP2") (pin "ITB") (pinfunction "ITB_ITB") (pintype "bidirectional"))
    )
    (net (code "89") (name "unconnected-(MCP2-PadNC{slash}CS)") (class "Default")
      (node (ref "MCP2") (pin "NC/CS") (pinfunction "NC/CS_NC/CS") (pintype "bidirectional"))
    )
    (net (code "90") (name "unconnected-(MCP2-PadNC{slash}SO)") (class "Default")
      (node (ref "MCP2") (pin "NC/SO") (pinfunction "NC/SO_NC/SO") (pintype "bidirectional"))
    )
    (net (code "91") (name "unconnected-(MCP2-PadVCC1)") (class "Default")
      (node (ref "MCP2") (pin "VCC1") (pinfunction "VCC1_VCC1") (pintype "bidirectional"))
    )
    (net (code "92") (name "unconnected-(U1-CLK-Pad38)") (class "Default")
      (node (ref "U1") (pin "38") (pinfunction "CLK_38") (pintype "input"))
    )
    (net (code "93") (name "unconnected-(U1-CMD-Pad18)") (class "Default")
      (node (ref "U1") (pin "18") (pinfunction "CMD_18") (pintype "bidirectional"))
    )
    (net (code "94") (name "unconnected-(U1-EN-Pad2)") (class "Default")
      (node (ref "U1") (pin "2") (pinfunction "EN_2") (pintype "input"))
    )
    (net (code "95") (name "unconnected-(U1-IO0-Pad33)") (class "Default")
      (node (ref "U1") (pin "33") (pinfunction "IO0_33") (pintype "bidirectional"))
    )
    (net (code "96") (name "unconnected-(U1-IO2-Pad34)") (class "Default")
      (node (ref "U1") (pin "34") (pinfunction "IO2_34") (pintype "bidirectional"))
    )
    (net (code "97") (name "unconnected-(U1-IO4-Pad32)") (class "Default")
      (node (ref "U1") (pin "32") (pinfunction "IO4_32") (pintype "bidirectional"))
    )
    (net (code "98") (name "unconnected-(U1-IO12-Pad13)") (class "Default")
      (node (ref "U1") (pin "13") (pinfunction "IO12_13") (pintype "bidirectional"))
    )
    (net (code "99") (name "unconnected-(U1-IO13-Pad15)") (class "Default")
      (node (ref "U1") (pin "15") (pinfunction "IO13_15") (pintype "bidirectional"))
    )
    (net (code "100") (name "unconnected-(U1-IO14-Pad12)") (class "Default")
      (node (ref "U1") (pin "12") (pinfunction "IO14_12") (pintype "bidirectional"))
    )
    (net (code "101") (name "unconnected-(U1-IO15-Pad35)") (class "Default")
      (node (ref "U1") (pin "35") (pinfunction "IO15_35") (pintype "bidirectional"))
    )
    (net (code "102") (name "unconnected-(U1-IO23-Pad21)") (class "Default")
      (node (ref "U1") (pin "21") (pinfunction "IO23_21") (pintype "bidirectional"))
    )
    (net (code "103") (name "unconnected-(U1-IO27-Pad11)") (class "Default")
      (node (ref "U1") (pin "11") (pinfunction "IO27_11") (pintype "bidirectional"))
    )
    (net (code "104") (name "unconnected-(U1-IO32-Pad7)") (class "Default")
      (node (ref "U1") (pin "7") (pinfunction "IO32_7") (pintype "bidirectional"))
    )
    (net (code "105") (name "unconnected-(U1-IO33-Pad8)") (class "Default")
      (node (ref "U1") (pin "8") (pinfunction "IO33_8") (pintype "bidirectional"))
    )
    (net (code "106") (name "unconnected-(U1-IO34-Pad5)") (class "Default")
      (node (ref "U1") (pin "5") (pinfunction "IO34_5") (pintype "bidirectional"))
    )
    (net (code "107") (name "unconnected-(U1-IO35-Pad6)") (class "Default")
      (node (ref "U1") (pin "6") (pinfunction "IO35_6") (pintype "bidirectional"))
    )
    (net (code "108") (name "unconnected-(U1-RXD0-Pad24)") (class "Default")
      (node (ref "U1") (pin "24") (pinfunction "RXD0_24") (pintype "input"))
    )
    (net (code "109") (name "unconnected-(U1-SD0-Pad37)") (class "Default")
      (node (ref "U1") (pin "37") (pinfunction "SD0_37") (pintype "bidirectional"))
    )
    (net (code "110") (name "unconnected-(U1-SD1-Pad36)") (class "Default")
      (node (ref "U1") (pin "36") (pinfunction "SD1_36") (pintype "bidirectional"))
    )
    (net (code "111") (name "unconnected-(U1-SD2-Pad16)") (class "Default")
      (node (ref "U1") (pin "16") (pinfunction "SD2_16") (pintype "bidirectional"))
    )
    (net (code "112") (name "unconnected-(U1-SD3-Pad17)") (class "Default")
      (node (ref "U1") (pin "17") (pinfunction "SD3_17") (pintype "bidirectional"))
    )
    (net (code "113") (name "unconnected-(U1-SENSOR_VN-Pad4)") (class "Default")
      (node (ref "U1") (pin "4") (pinfunction "SENSOR_VN_4") (pintype "input"))
    )
    (net (code "114") (name "unconnected-(U1-SENSOR_VP-Pad3)") (class "Default")
      (node (ref "U1") (pin "3") (pinfunction "SENSOR_VP_3") (pintype "input"))
    )
    (net (code "115") (name "unconnected-(U1-TXD0-Pad23)") (class "Default")
      (node (ref "U1") (pin "23") (pinfunction "TXD0_23") (pintype "output"))
    )
  )
)
